# ic555-astable.net
KiCad netlist of a schematic drawn in EAGLE
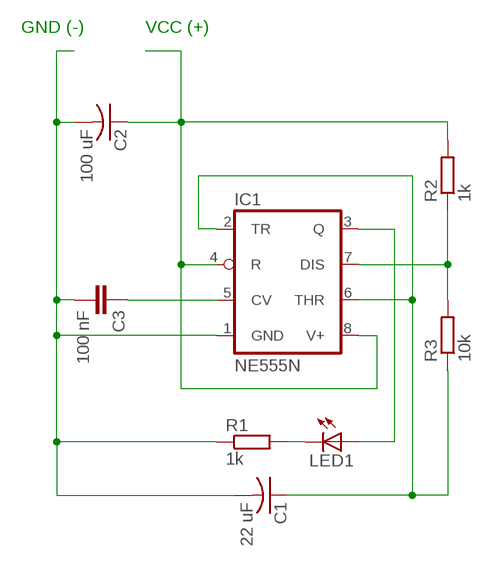
[diagram p0: schematic, sheet 1]

(export (version "E")
  (design (tool "Eeschema 10.0.6"))
  (components
    (comp (ref "C1")
      (value "22 uF")
      (footprint "eagle-import:C050-035X075")
      (libsource (lib "eagle-import") (part "C-US050-035X075"))
    )
    (comp (ref "C2")
      (value "100 uF")
      (footprint "eagle-import:C050-035X075")
      (libsource (lib "eagle-import") (part "C-US050-035X075"))
    )
    (comp (ref "C3")
      (value "100 nF")
      (footprint "eagle-import:C050-035X075")
      (libsource (lib "eagle-import") (part "C-EU050-035X075"))
    )
    (comp (ref "IC1")
      (value "NE555N")
      (footprint "eagle-import:DIL08")
      (libsource (lib "eagle-import") (part "555NNE"))
    )
    (comp (ref "LED1")
      (value "LED5MM")
      (footprint "eagle-import:LED5MM")
      (libsource (lib "eagle-import") (part "LED5MM"))
    )
    (comp (ref "R1")
      (value "1k")
      (footprint "eagle-import:0204_7")
      (libsource (lib "eagle-import") (part "R-EU_0204/7"))
    )
    (comp (ref "R2")
      (value "1k")
      (footprint "eagle-import:0204_7")
      (libsource (lib "eagle-import") (part "R-EU_0204/7"))
    )
    (comp (ref "R3")
      (value "10k")
      (footprint "eagle-import:0204_7")
      (libsource (lib "eagle-import") (part "R-EU_0204/7"))
    )
  )
  (nets
    (net (code "1") (name "Net-(IC1-CV)") (class "Default")
      (node (ref "C3") (pin "1") (pinfunction "1_1") (pintype "passive"))
      (node (ref "IC1") (pin "5") (pinfunction "CV_5") (pintype "input"))
    )
    (net (code "2") (name "Net-(IC1-DIS)") (class "Default")
      (node (ref "IC1") (pin "7") (pinfunction "DIS_7") (pintype "input"))
      (node (ref "R2") (pin "1") (pinfunction "1_1") (pintype "passive"))
      (node (ref "R3") (pin "2") (pinfunction "2_2") (pintype "passive"))
    )
    (net (code "3") (name "Net-(IC1-GND)") (class "Default")
      (node (ref "C1") (pin "2") (pinfunction "2_2") (pintype "passive"))
      (node (ref "C2") (pin "2") (pinfunction "2_2") (pintype "passive"))
      (node (ref "C3") (pin "2") (pinfunction "2_2") (pintype "passive"))
      (node (ref "IC1") (pin "1") (pinfunction "GND_1") (pintype "power_in"))
      (node (ref "R1") (pin "1") (pinfunction "1_1") (pintype "passive"))
    )
    (net (code "4") (name "Net-(IC1-Q)") (class "Default")
      (node (ref "IC1") (pin "3") (pinfunction "Q_3") (pintype "output"))
      (node (ref "LED1") (pin "A") (pinfunction "A_A") (pintype "passive"))
    )
    (net (code "5") (name "Net-(IC1-R)") (class "Default")
      (node (ref "C2") (pin "1") (pinfunction "1_1") (pintype "passive"))
      (node (ref "IC1") (pin "4") (pinfunction "R_4") (pintype "input"))
      (node (ref "IC1") (pin "8") (pinfunction "V+_8") (pintype "power_in"))
      (node (ref "R2") (pin "2") (pinfunction "2_2") (pintype "passive"))
    )
    (net (code "6") (name "Net-(IC1-THR)") (class "Default")
      (node (ref "C1") (pin "1") (pinfunction "1_1") (pintype "passive"))
      (node (ref "IC1") (pin "2") (pinfunction "TR_2") (pintype "input"))
      (node (ref "IC1") (pin "6") (pinfunction "THR_6") (pintype "input"))
      (node (ref "R3") (pin "1") (pinfunction "1_1") (pintype "passive"))
    )
    (net (code "7") (name "Net-(LED1-C)") (class "Default")
      (node (ref "LED1") (pin "K") (pinfunction "C_K") (pintype "passive"))
      (node (ref "R1") (pin "2") (pinfunction "2_2") (pintype "passive"))
    )
  )
)
